# relais_platine.net
KiCad netlist of a schematic drawn in EAGLE
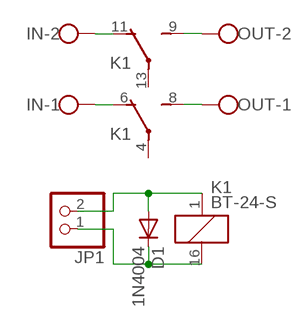
[diagram p0: schematic, sheet 1]

(export (version "E")
  (design (tool "Eeschema 10.0.6"))
  (components
    (comp (ref "D1")
      (value "1N4004")
      (footprint "eagle-import:DO41-10")
      (libsource (lib "eagle-import") (part "1N4004"))
    )
    (comp (ref "IN")
      (value "W237-102")
      (footprint "eagle-import:W237-102")
      (fields (field (name "MPN") "237-102"))
      (libsource (lib "eagle-import") (part "W237-102"))
    )
    (comp (ref "JP1")
      (value "PINHD-1X2/90")
      (footprint "eagle-import:1X02_90")
      (libsource (lib "eagle-import") (part "PINHD-1X2/90"))
    )
    (comp (ref "K1")
      (value "BT-24-S")
      (footprint "eagle-import:BT-XX-S")
      (libsource (lib "eagle-import") (part "BT--S24"))
    )
    (comp (ref "OUT")
      (value "W237-102")
      (footprint "eagle-import:W237-102")
      (fields (field (name "MPN") "237-102"))
      (libsource (lib "eagle-import") (part "W237-102"))
    )
  )
  (nets
    (net (code "1") (name "Net-(D1-PadA)") (class "Default")
      (node (ref "D1") (pin "A") (pinfunction "A_A") (pintype "passive"))
      (node (ref "JP1") (pin "2") (pinfunction "2_2") (pintype "passive"))
      (node (ref "K1") (pin "1") (pinfunction "1_1") (pintype "passive"))
    )
    (net (code "2") (name "Net-(INA-KL)") (class "Default")
      (node (ref "IN") (pin "1") (pinfunction "KL_1") (pintype "passive"))
      (node (ref "K1") (pin "6") (pinfunction "O_6") (pintype "passive"))
    )
    (net (code "3") (name "Net-(INB-KL)") (class "Default")
      (node (ref "IN") (pin "2") (pinfunction "KL_2") (pintype "passive"))
      (node (ref "K1") (pin "11") (pinfunction "O_11") (pintype "passive"))
    )
    (net (code "4") (name "Net-(K1A-S)") (class "Default")
      (node (ref "K1") (pin "8") (pinfunction "S_8") (pintype "passive"))
      (node (ref "OUT") (pin "1") (pinfunction "KL_1") (pintype "passive"))
    )
    (net (code "5") (name "Net-(K1B-S)") (class "Default")
      (node (ref "K1") (pin "9") (pinfunction "S_9") (pintype "passive"))
      (node (ref "OUT") (pin "2") (pinfunction "KL_2") (pintype "passive"))
    )
    (net (code "6") (name "Net-(K1C-2)") (class "Default")
      (node (ref "D1") (pin "C") (pinfunction "C_C") (pintype "passive"))
      (node (ref "JP1") (pin "1") (pinfunction "1_1") (pintype "passive"))
      (node (ref "K1") (pin "16") (pinfunction "2_16") (pintype "passive"))
    )
    (net (code "7") (name "unconnected-(K1A-P-Pad4)") (class "Default")
      (node (ref "K1") (pin "4") (pinfunction "P_4") (pintype "passive"))
    )
    (net (code "8") (name "unconnected-(K1B-P-Pad13)") (class "Default")
      (node (ref "K1") (pin "13") (pinfunction "P_13") (pintype "passive"))
    )
  )
)
